# G1000_Encoder_Base.net
KiCad netlist of a schematic drawn in EasyEDA
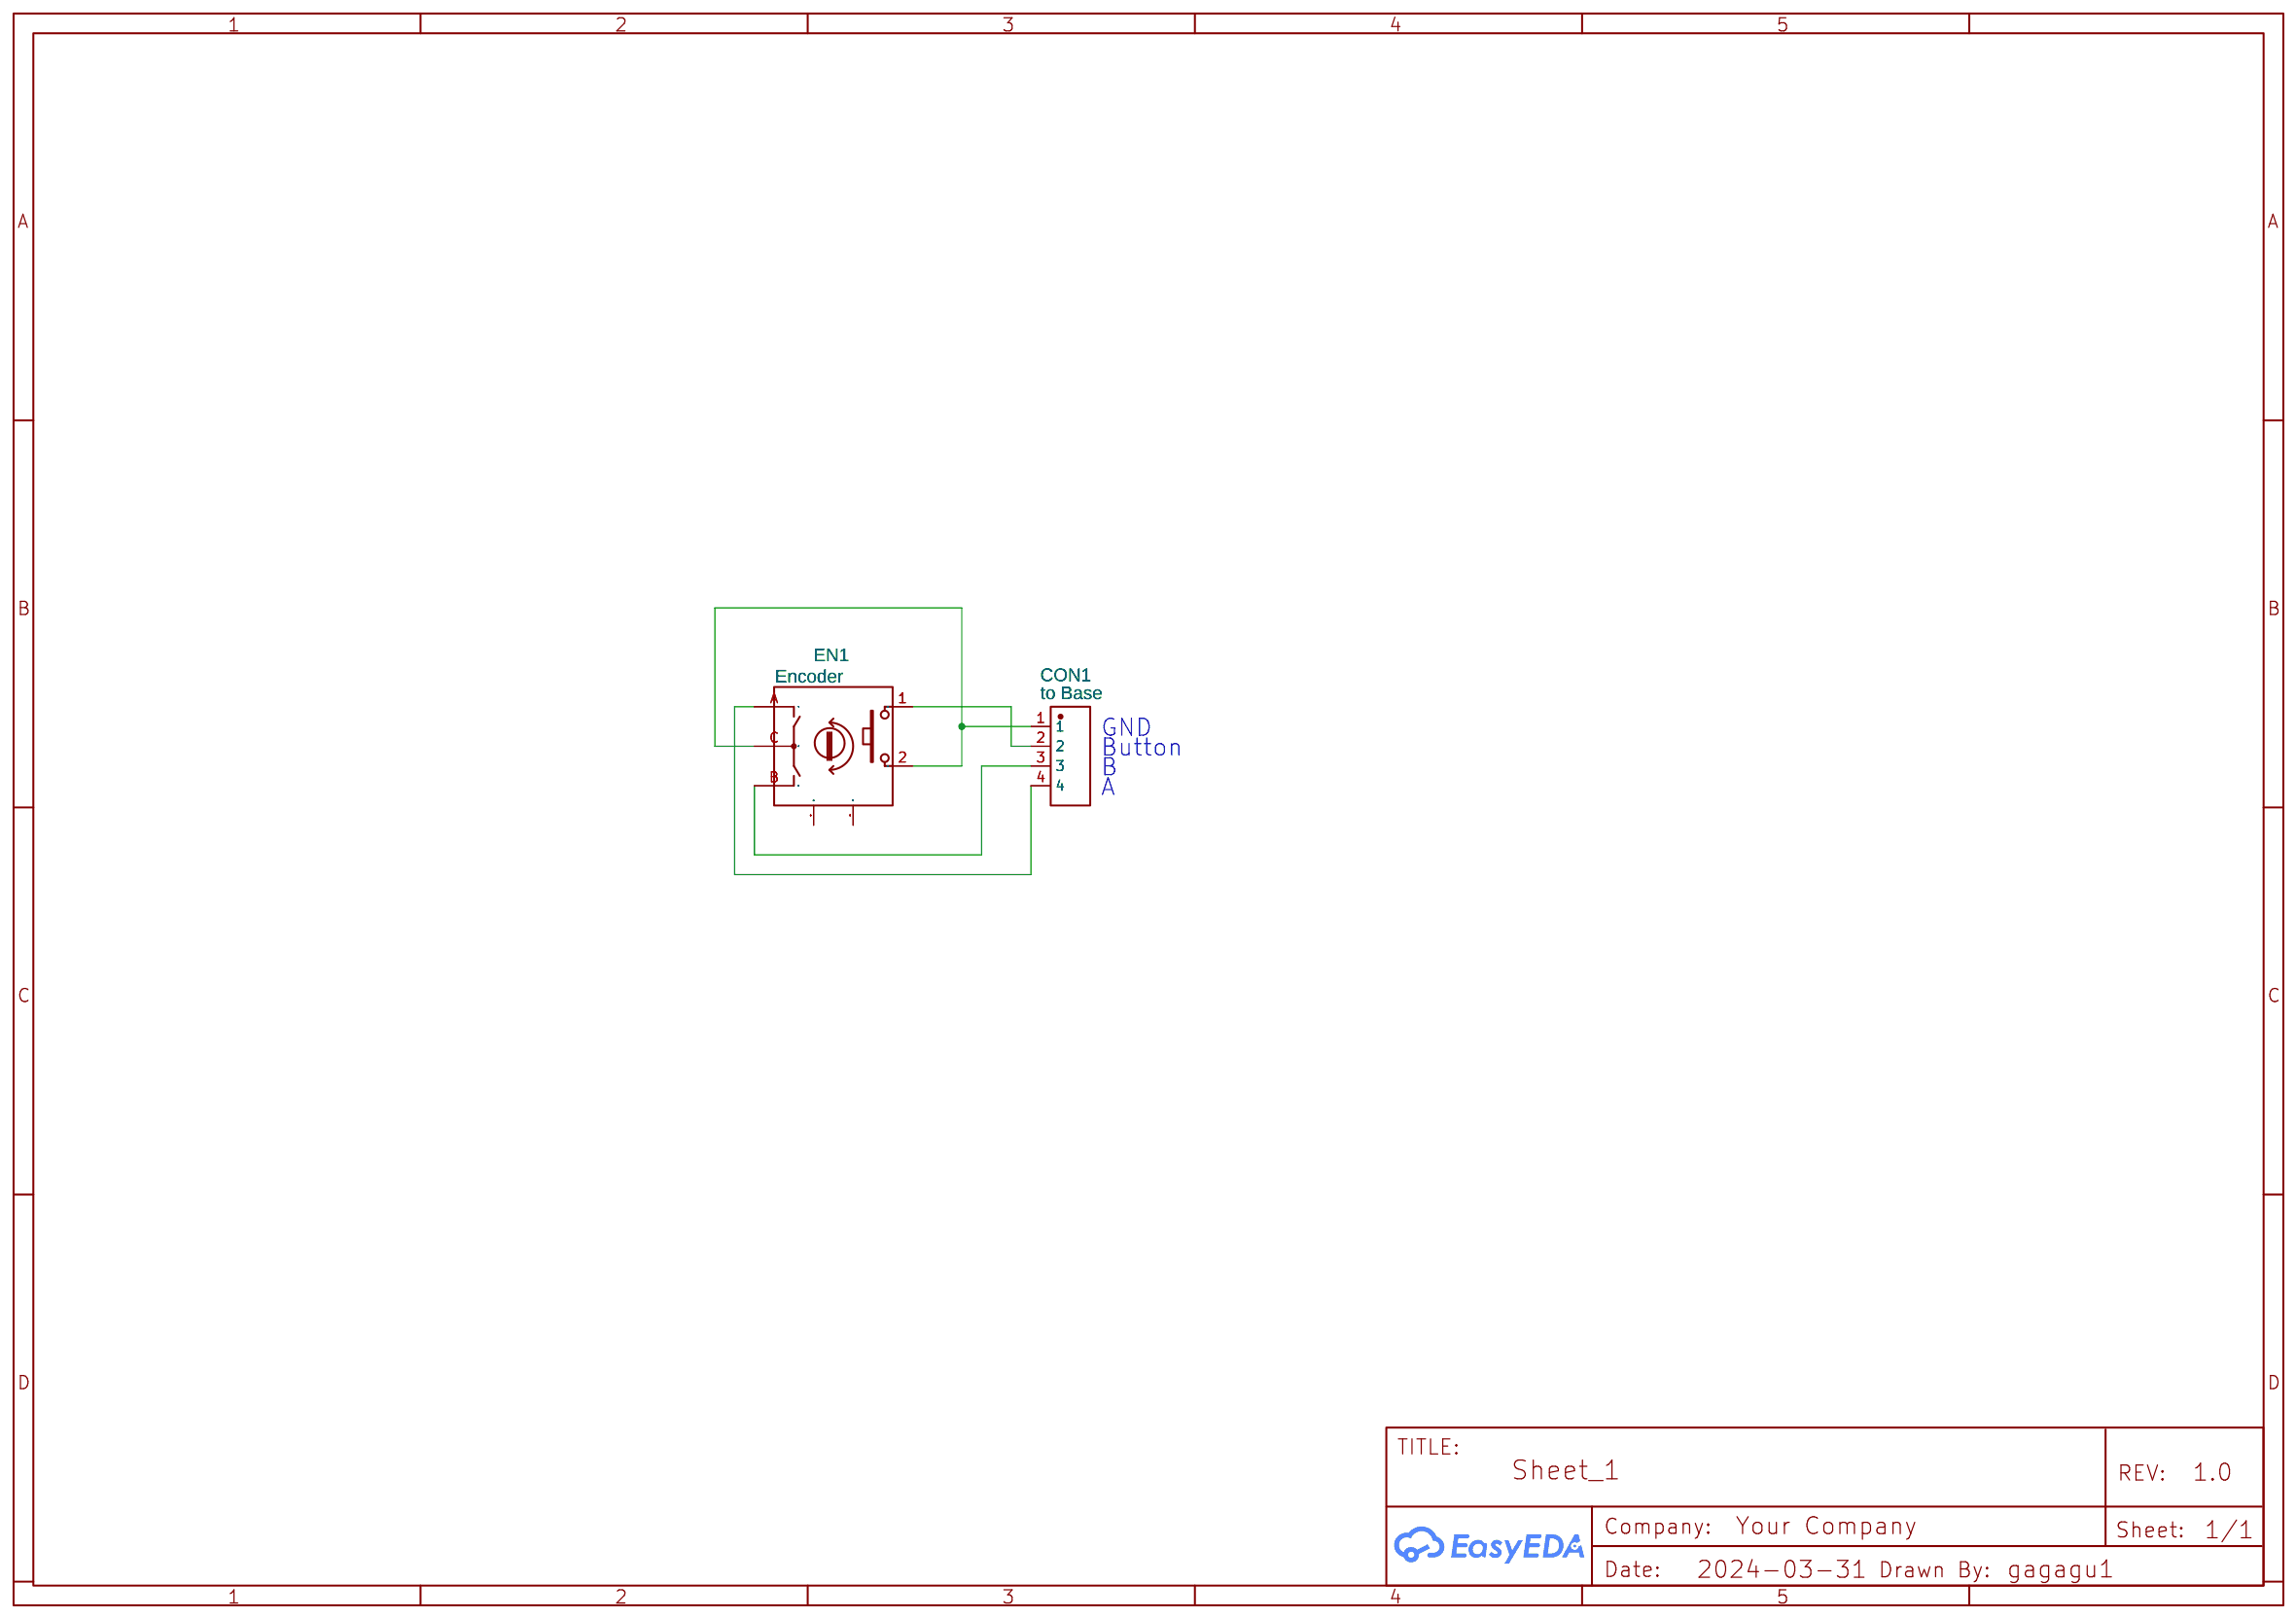
[diagram p0: schematic sheet]

(export (version "E")
  (design (tool "Eeschema 10.0.6"))
  (components
    (comp (ref "CON1")
      (value "to Base")
      (fields (field (name "Manufacturer Part") "XH-4A绿色") (field (name "Manufacturer") "BOOMELE(博穆精密)"))
      (libsource (lib "") (part "ARUN-CONN-TH_XH-4A"))
    )
    (comp (ref "EN1")
      (value "Encoder")
      (fields (field (name "Manufacturer Part") "PEC11R-4015F-S0024") (field (name "Manufacturer") "BOURNS"))
      (libsource (lib "") (part "PEC11R-4015F-S0024"))
    )
  )
  (nets
    (net (code "1") (name "Net-(CON1-Pad1)") (class "Default")
      (node (ref "CON1") (pin "1") (pinfunction "1_1") (pintype "unspecified"))
      (node (ref "EN1") (pin "2") (pinfunction "2_2") (pintype "unspecified"))
      (node (ref "EN1") (pin "C") (pinfunction "C_C") (pintype "unspecified"))
    )
    (net (code "2") (name "Net-(CON1-Pad2)") (class "Default")
      (node (ref "CON1") (pin "2") (pinfunction "2_2") (pintype "unspecified"))
      (node (ref "EN1") (pin "1") (pinfunction "1_1") (pintype "unspecified"))
    )
    (net (code "3") (name "Net-(CON1-Pad3)") (class "Default")
      (node (ref "CON1") (pin "3") (pinfunction "3_3") (pintype "unspecified"))
      (node (ref "EN1") (pin "B") (pinfunction "B_B") (pintype "unspecified"))
    )
    (net (code "4") (name "Net-(CON1-Pad4)") (class "Default")
      (node (ref "CON1") (pin "4") (pinfunction "4_4") (pintype "unspecified"))
      (node (ref "EN1") (pin "A") (pinfunction "A_A") (pintype "unspecified"))
    )
    (net (code "5") (name "unconnected-(EN1-PadMT1)") (class "Default")
      (node (ref "EN1") (pin "MT1") (pinfunction "MT1_MT1") (pintype "unspecified"))
    )
    (net (code "6") (name "unconnected-(EN1-PadMT2)") (class "Default")
      (node (ref "EN1") (pin "MT2") (pinfunction "MT2_MT2") (pintype "unspecified"))
    )
  )
)
